# MacSet-L-V2_0_0_1.net
KiCad netlist of a schematic drawn in Altium Designer
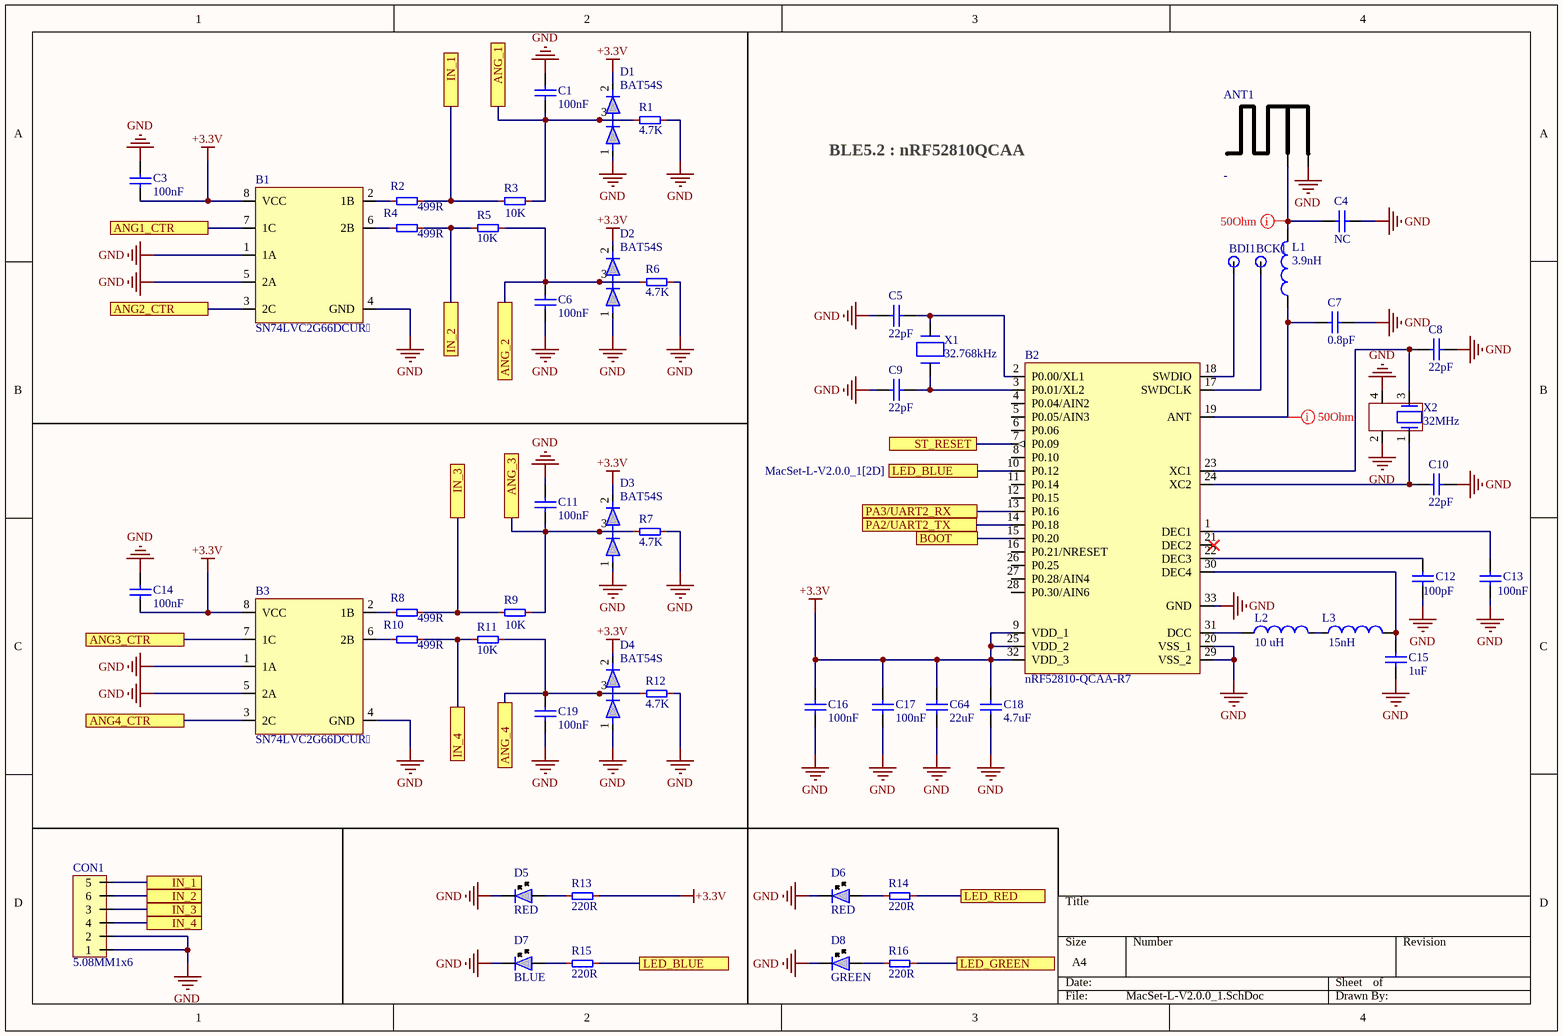
[diagram p0: MacSet-L-V2.0.0_1.SchDoc]

(export (version "E")
  (design (tool "Eeschema 10.0.6"))
  (components
    (comp (ref "ANT1")
      (value "-")
      (footprint "2.4GHz PCB Anttenna")
      (description "2.4GHq Inverted F antenna 1.6mm Thikness")
      (libsource (lib "macnman_2.0") (part "2.4GHz Antenna"))
    )
    (comp (ref "B1")
      (value "SN74LVC2G66DCUR")
      (footprint "SOP50P310X90-8N")
      (description "2-Channel, 1:1 Analog Switch with Low On-State Resistance")
      (fields
        (field (name "MANUFACTURER") "Texas Instruments")
        (field (name "MANUFACTURER_PART_NUMBER") "SN74LVC2G66DCUR")
      )
      (libsource (lib "macnman_2.0") (part "SN74LVC2G66DCUR"))
    )
    (comp (ref "B2")
      (value "nRF52810-QCAA-R7")
      (footprint "QFN50P500X500X95-33N")
      (fields (field (name "MANUFACTURER") "Nordic Semiconductor"))
      (libsource (lib "macnman_2.0") (part "nRF52810-QCAA-R7"))
    )
    (comp (ref "B3")
      (value "SN74LVC2G66DCUR")
      (footprint "SOP50P310X90-8N")
      (description "2-Channel, 1:1 Analog Switch with Low On-State Resistance")
      (fields
        (field (name "MANUFACTURER") "Texas Instruments")
        (field (name "MANUFACTURER_PART_NUMBER") "SN74LVC2G66DCUR")
      )
      (libsource (lib "macnman_2.0") (part "SN74LVC2G66DCUR"))
    )
    (comp (ref "BCK1")
      (value "-")
      (footprint "TH_Pad")
      (description "Through Hole pad 1mm 0.5mm Hole")
      (libsource (lib "macnman_2.0") (part "TH_PAD"))
    )
    (comp (ref "BDI1")
      (value "-")
      (footprint "TH_Pad")
      (description "Through Hole pad 1mm 0.5mm Hole")
      (libsource (lib "macnman_2.0") (part "TH_PAD"))
    )
    (comp (ref "C1")
      (value "100nF")
      (footprint "CAP0402")
      (description "Ceramic Capacitor C0G, NP0 0402 100nF 35V")
      (fields
        (field (name "MANUFACTURER_PART_NUMBER") "GRM155R61A104KA01J")
        (field (name "MANUFACTURER") "MURATA")
      )
      (libsource (lib "macnman_2.0") (part "Capa_0402"))
    )
    (comp (ref "C3")
      (value "100nF")
      (footprint "CAP0402")
      (description "Ceramic Capacitor C0G, NP0 0402 100nF 35V")
      (fields
        (field (name "MANUFACTURER_PART_NUMBER") "GRM155R61A104KA01J")
        (field (name "MANUFACTURER") "MURATA")
      )
      (libsource (lib "macnman_2.0") (part "Capa_0402"))
    )
    (comp (ref "C4") (value "NC") (footprint "CAP0402") (libsource (lib "macnman_2.0") (part "Capa_0402")))
    (comp (ref "C5")
      (value "22pF")
      (footprint "CAP0402")
      (description "Multilayer Ceramic Capacitors MLCC - SMD/SMT 50 V 22pF C0G 0402 5%")
      (fields
        (field (name "MANUFACTURER_PART_NUMBER") "GCM1555C1H220JA16D")
        (field (name "MANUFACTURER") "Murata")
      )
      (libsource (lib "macnman_2.0") (part "Capa_0402"))
    )
    (comp (ref "C6")
      (value "100nF")
      (footprint "CAP0402")
      (description "Ceramic Capacitor C0G, NP0 0402 100nF 35V")
      (fields
        (field (name "MANUFACTURER_PART_NUMBER") "GRM155R61A104KA01J")
        (field (name "MANUFACTURER") "MURATA")
      )
      (libsource (lib "macnman_2.0") (part "Capa_0402"))
    )
    (comp (ref "C7")
      (value "0.8pF")
      (footprint "CAP0402")
      (description "Ceramic Capacitor C0G, NP0 0402 0.8pF 50V")
      (fields
        (field (name "MANUFACTURER_PART_NUMBER") "CC0402BRNPO9BNR80")
        (field (name "MANUFACTURER") "YAGEO")
      )
      (libsource (lib "macnman_2.0") (part "Capa_0402"))
    )
    (comp (ref "C8")
      (value "22pF")
      (footprint "CAP0402")
      (description "Multilayer Ceramic Capacitors MLCC - SMD/SMT 50 V 22pF C0G 0402 5%")
      (fields
        (field (name "MANUFACTURER_PART_NUMBER") "GCM1555C1H220JA16D")
        (field (name "MANUFACTURER") "Murata")
      )
      (libsource (lib "macnman_2.0") (part "Capa_0402"))
    )
    (comp (ref "C9")
      (value "22pF")
      (footprint "CAP0402")
      (description "Multilayer Ceramic Capacitors MLCC - SMD/SMT 50 V 22pF C0G 0402 5%")
      (fields
        (field (name "MANUFACTURER_PART_NUMBER") "GCM1555C1H220JA16D")
        (field (name "MANUFACTURER") "Murata")
      )
      (libsource (lib "macnman_2.0") (part "Capa_0402"))
    )
    (comp (ref "C10")
      (value "22pF")
      (footprint "CAP0402")
      (description "Multilayer Ceramic Capacitors MLCC - SMD/SMT 50 V 22pF C0G 0402 5%")
      (fields
        (field (name "MANUFACTURER_PART_NUMBER") "GCM1555C1H220JA16D")
        (field (name "MANUFACTURER") "Murata")
      )
      (libsource (lib "macnman_2.0") (part "Capa_0402"))
    )
    (comp (ref "C11")
      (value "100nF")
      (footprint "CAP0402")
      (description "Ceramic Capacitor C0G, NP0 0402 100nF 35V")
      (fields
        (field (name "MANUFACTURER_PART_NUMBER") "GRM155R61A104KA01J")
        (field (name "MANUFACTURER") "MURATA")
      )
      (libsource (lib "macnman_2.0") (part "Capa_0402"))
    )
    (comp (ref "C12")
      (value "100pF")
      (footprint "CAP0402")
      (description "Ceramic Capacitor C0G, NP0 0402 100pF 50V")
      (fields
        (field (name "MANUFACTURER_PART_NUMBER") "GRM1555C1H101GA01D")
        (field (name "MANUFACTURER") "MURATA")
      )
      (libsource (lib "macnman_2.0") (part "Capa_0402"))
    )
    (comp (ref "C13")
      (value "100nF")
      (footprint "CAP0402")
      (description "Ceramic Capacitor X7R 0402 100nF 16V")
      (fields
        (field (name "MANUFACTURER_PART_NUMBER") "GRM155R71C104JA88D")
        (field (name "MANUFACTURER") "MURATA")
      )
      (libsource (lib "macnman_2.0") (part "Capa_0402"))
    )
    (comp (ref "C14")
      (value "100nF")
      (footprint "CAP0402")
      (description "Ceramic Capacitor C0G, NP0 0402 100nF 35V")
      (fields
        (field (name "MANUFACTURER_PART_NUMBER") "GRM155R61A104KA01J")
        (field (name "MANUFACTURER") "MURATA")
      )
      (libsource (lib "macnman_2.0") (part "Capa_0402"))
    )
    (comp (ref "C15")
      (value "1uF")
      (footprint "CAP0603")
      (description "MLCC - SMD/SMT 1 uF 16 VDC 10% 0603 X5R")
      (fields
        (field (name "MANUFACTURER_PART_NUMBER") "GRM188R61C105MA12D")
        (field (name "MANUFACTURER") "MURATA")
      )
      (libsource (lib "macnman_2.0") (part "Capa_0603"))
    )
    (comp (ref "C16")
      (value "100nF")
      (footprint "CAP0402")
      (description "Ceramic Capacitor X7R 0402 100nF 16V")
      (fields
        (field (name "MANUFACTURER_PART_NUMBER") "GRM155R71C104JA88D")
        (field (name "MANUFACTURER") "MURATA")
      )
      (libsource (lib "macnman_2.0") (part "Capa_0402"))
    )
    (comp (ref "C17")
      (value "100nF")
      (footprint "CAP0402")
      (description "Ceramic Capacitor X7R 0402 100nF 16V")
      (fields
        (field (name "MANUFACTURER_PART_NUMBER") "GRM155R71C104JA88D")
        (field (name "MANUFACTURER") "MURATA")
      )
      (libsource (lib "macnman_2.0") (part "Capa_0402"))
    )
    (comp (ref "C18")
      (value "4.7uF")
      (footprint "CAP0603")
      (description "MLCC - SMD/SMT 4.7 uF 16 VDC 10% 0603 X5R")
      (fields
        (field (name "MANUFACTURER_PART_NUMBER") "CL10A475KQ8NNNC")
        (field (name "MANUFACTURER") "Samsung Electro-Mechanics")
      )
      (libsource (lib "macnman_2.0") (part "Capa_0603"))
    )
    (comp (ref "C19")
      (value "100nF")
      (footprint "CAP0402")
      (description "Ceramic Capacitor C0G, NP0 0402 100nF 35V")
      (fields
        (field (name "MANUFACTURER_PART_NUMBER") "GRM155R61A104KA01J")
        (field (name "MANUFACTURER") "MURATA")
      )
      (libsource (lib "macnman_2.0") (part "Capa_0402"))
    )
    (comp (ref "C64")
      (value "22uF")
      (footprint "CAP0805")
      (description "MLCC - SMD/SMT 22uF 10VDC 20% 0805 X6S")
      (fields
        (field (name "MANUFACTURER_PART_NUMBER") "CC0805KKX7R6BB226")
        (field (name "MANUFACTURER") "MURATA")
      )
      (libsource (lib "macnman_2.0") (part "Capa_0805"))
    )
    (comp (ref "CON1")
      (value "5.08MM1x6")
      (footprint "Screw Terminal Block 5.08x6")
      (description "5.08mm 1*6 Screw Terminal Block")
      (fields (field (name "MANUFACTURER") "XINYA"))
      (libsource (lib "macnman_2.0") (part "Screw Terminal Block 6x1 5.08mm"))
    )
    (comp (ref "D1")
      (value "BAT54S")
      (footprint "SOT23")
      (description "BAT54S Schottky Diodes & Rectifiers SS SHKY DIO 30V TR")
      (fields (field (name "MANUFACTURER_PART_NUMBER") "Nexperia") (field (name "MANUFACTURER") "BAT54S,235"))
      (libsource (lib "macnman_2.0") (part "BAT54SWT1G"))
    )
    (comp (ref "D2")
      (value "BAT54S")
      (footprint "SOT23")
      (description "BAT54S Schottky Diodes & Rectifiers SS SHKY DIO 30V TR")
      (fields (field (name "MANUFACTURER_PART_NUMBER") "Nexperia") (field (name "MANUFACTURER") "BAT54S,235"))
      (libsource (lib "macnman_2.0") (part "BAT54SWT1G"))
    )
    (comp (ref "D3")
      (value "BAT54S")
      (footprint "SOT23")
      (description "BAT54S Schottky Diodes & Rectifiers SS SHKY DIO 30V TR")
      (fields (field (name "MANUFACTURER_PART_NUMBER") "Nexperia") (field (name "MANUFACTURER") "BAT54S,235"))
      (libsource (lib "macnman_2.0") (part "BAT54SWT1G"))
    )
    (comp (ref "D4")
      (value "BAT54S")
      (footprint "SOT23")
      (description "BAT54S Schottky Diodes & Rectifiers SS SHKY DIO 30V TR")
      (fields (field (name "MANUFACTURER_PART_NUMBER") "Nexperia") (field (name "MANUFACTURER") "BAT54S,235"))
      (libsource (lib "macnman_2.0") (part "BAT54SWT1G"))
    )
    (comp (ref "D5")
      (value "RED")
      (footprint "LED_3MM")
      (description "LED 3MM Through Hole RED")
      (libsource (lib "macnman_2.0") (part "LED_3MM"))
    )
    (comp (ref "D6")
      (value "RED")
      (footprint "LED_3MM")
      (description "LED 3MM Through Hole RED")
      (libsource (lib "macnman_2.0") (part "LED_3MM"))
    )
    (comp (ref "D7")
      (value "BLUE")
      (footprint "LED_3MM")
      (description "LED 3MM Through Hole BLUE")
      (libsource (lib "macnman_2.0") (part "LED_3MM"))
    )
    (comp (ref "D8")
      (value "GREEN")
      (footprint "LED_3MM")
      (description "LED 3MM Through Hole GREEN")
      (libsource (lib "macnman_2.0") (part "LED_3MM"))
    )
    (comp (ref "L1")
      (value "3.9nH")
      (footprint "IND_0402")
      (description "3.9nH High frequency chip inductor ±5%  0402")
      (fields
        (field (name "MANUFACTURER_PART_NUMBER") "LQG15HS3N9B02D")
        (field (name "MANUFACTURER") "Murata")
      )
      (libsource (lib "macnman_2.0") (part "Inductor"))
    )
    (comp (ref "L2")
      (value "10 uH")
      (footprint "IND_0603")
      (description "250mA 10uH ±20% 90mΩ 0603 Inductors")
      (fields
        (field (name "MANUFACTURER_PART_NUMBER") "MLZ1608M100WT000")
        (field (name "MANUFACTURER") "TDK")
      )
      (libsource (lib "macnman_2.0") (part "MCD-01330"))
    )
    (comp (ref "L3")
      (value "15nH")
      (footprint "IND_0402")
      (description "400mA 15nH ±5% 350mΩ 0402 Inductors")
      (fields
        (field (name "MANUFACTURER_PART_NUMBER") "MLG1005S15NJT000")
        (field (name "MANUFACTURER") "Murata")
      )
      (libsource (lib "macnman_2.0") (part "MCD-01330"))
    )
    (comp (ref "R1")
      (value "4.7K")
      (footprint "RESC0402")
      (description "Thin Film Resistors - SMD 4.7Kohms 0.1% 0402 25ppm")
      (fields
        (field (name "MANUFACTURER_PART_NUMBER") "RT0402BRD074K7L")
        (field (name "MANUFACTURER") "YAGEO")
      )
      (libsource (lib "macnman_2.0") (part "RES_0402"))
    )
    (comp (ref "R2")
      (value "499R")
      (footprint "RESC0805")
      (description "Thin Film Resistors - SMD 499ohms 0.1% 25ppm")
      (fields
        (field (name "MANUFACTURER_PART_NUMBER") "TNPW0805499RBEEA")
        (field (name "MANUFACTURER") "Vishay")
      )
      (libsource (lib "macnman_2.0") (part "RES_0805"))
    )
    (comp (ref "R3")
      (value "10K")
      (footprint "RESC0402")
      (description "Thick Film Resistors - SMD 1/16watt 10Kohms 0.1% 0402 Commercial Use")
      (fields
        (field (name "MANUFACTURER_PART_NUMBER") "MCS04020D1002BE000")
        (field (name "MANUFACTURER") "Vishay")
      )
      (libsource (lib "macnman_2.0") (part "RES_0402"))
    )
    (comp (ref "R4")
      (value "499R")
      (footprint "RESC0805")
      (description "Thin Film Resistors - SMD 499ohms 0.1% 25ppm")
      (fields
        (field (name "MANUFACTURER_PART_NUMBER") "TNPW0805499RBEEA")
        (field (name "MANUFACTURER") "Vishay")
      )
      (libsource (lib "macnman_2.0") (part "RES_0805"))
    )
    (comp (ref "R5")
      (value "10K")
      (footprint "RESC0402")
      (description "Thick Film Resistors - SMD 1/16watt 10Kohms 0.1% 0402 Commercial Use")
      (fields
        (field (name "MANUFACTURER_PART_NUMBER") "MCS04020D1002BE000")
        (field (name "MANUFACTURER") "Vishay")
      )
      (libsource (lib "macnman_2.0") (part "RES_0402"))
    )
    (comp (ref "R6")
      (value "4.7K")
      (footprint "RESC0402")
      (description "Thin Film Resistors - SMD 4.7Kohms 0.1% 0402 25ppm")
      (fields
        (field (name "MANUFACTURER_PART_NUMBER") "RT0402BRD074K7L")
        (field (name "MANUFACTURER") "YAGEO")
      )
      (libsource (lib "macnman_2.0") (part "RES_0402"))
    )
    (comp (ref "R7")
      (value "4.7K")
      (footprint "RESC0402")
      (description "Thin Film Resistors - SMD 4.7Kohms 0.1% 0402 25ppm")
      (fields
        (field (name "MANUFACTURER_PART_NUMBER") "RT0402BRD074K7L")
        (field (name "MANUFACTURER") "YAGEO")
      )
      (libsource (lib "macnman_2.0") (part "RES_0402"))
    )
    (comp (ref "R8")
      (value "499R")
      (footprint "RESC0805")
      (description "Thin Film Resistors - SMD 499ohms 0.1% 25ppm")
      (fields
        (field (name "MANUFACTURER_PART_NUMBER") "TNPW0805499RBEEA")
        (field (name "MANUFACTURER") "Vishay")
      )
      (libsource (lib "macnman_2.0") (part "RES_0805"))
    )
    (comp (ref "R9")
      (value "10K")
      (footprint "RESC0402")
      (description "Thick Film Resistors - SMD 1/16watt 10Kohms 0.1% 0402 Commercial Use")
      (fields
        (field (name "MANUFACTURER_PART_NUMBER") "MCS04020D1002BE000")
        (field (name "MANUFACTURER") "Vishay")
      )
      (libsource (lib "macnman_2.0") (part "RES_0402"))
    )
    (comp (ref "R10")
      (value "499R")
      (footprint "RESC0805")
      (description "Thin Film Resistors - SMD 499ohms 0.1% 25ppm")
      (fields
        (field (name "MANUFACTURER_PART_NUMBER") "TNPW0805499RBEEA")
        (field (name "MANUFACTURER") "Vishay")
      )
      (libsource (lib "macnman_2.0") (part "RES_0805"))
    )
    (comp (ref "R11")
      (value "10K")
      (footprint "RESC0402")
      (description "Thick Film Resistors - SMD 1/16watt 10Kohms 0.1% 0402 Commercial Use")
      (fields
        (field (name "MANUFACTURER_PART_NUMBER") "MCS04020D1002BE000")
        (field (name "MANUFACTURER") "Vishay")
      )
      (libsource (lib "macnman_2.0") (part "RES_0402"))
    )
    (comp (ref "R12")
      (value "4.7K")
      (footprint "RESC0402")
      (description "Thin Film Resistors - SMD 4.7Kohms 0.1% 0402 25ppm")
      (fields
        (field (name "MANUFACTURER_PART_NUMBER") "RT0402BRD074K7L")
        (field (name "MANUFACTURER") "YAGEO")
      )
      (libsource (lib "macnman_2.0") (part "RES_0402"))
    )
    (comp (ref "R13")
      (value "220R")
      (footprint "RESC0402")
      (description "Thick Film Resistors - SMD 1/16watt 220R 0402 1% Commercial Use")
      (fields
        (field (name "MANUFACTURER_PART_NUMBER") "RC0402FR-07220RL")
        (field (name "MANUFACTURER") "Vishay")
      )
      (libsource (lib "macnman_2.0") (part "RES_0402"))
    )
    (comp (ref "R14")
      (value "220R")
      (footprint "RESC0402")
      (description "Thick Film Resistors - SMD 1/16watt 220R 0402 1% Commercial Use")
      (fields
        (field (name "MANUFACTURER_PART_NUMBER") "RC0402FR-07220RL")
        (field (name "MANUFACTURER") "Vishay")
      )
      (libsource (lib "macnman_2.0") (part "RES_0402"))
    )
    (comp (ref "R15")
      (value "220R")
      (footprint "RESC0402")
      (description "Thick Film Resistors - SMD 1/16watt 220R 0402 1% Commercial Use")
      (fields
        (field (name "MANUFACTURER_PART_NUMBER") "RC0402FR-07220RL")
        (field (name "MANUFACTURER") "Vishay")
      )
      (libsource (lib "macnman_2.0") (part "RES_0402"))
    )
    (comp (ref "R16")
      (value "220R")
      (footprint "RESC0402")
      (description "Thick Film Resistors - SMD 1/16watt 220R 0402 1% Commercial Use")
      (fields
        (field (name "MANUFACTURER_PART_NUMBER") "RC0402FR-07220RL")
        (field (name "MANUFACTURER") "Vishay")
      )
      (libsource (lib "macnman_2.0") (part "RES_0402"))
    )
    (comp (ref "X1")
      (value "32.768kHz")
      (footprint "OSC_3215")
      (description "Crystal Osc 3215 32.768kHz 12pF")
      (fields
        (field (name "MANUFACTURER_PART_NUMBER") "ECS-.327-12.5-34B-TR")
        (field (name "MANUFACTURER") "ECS")
      )
      (libsource (lib "macnman_2.0") (part "OSC_2012"))
    )
    (comp (ref "X2")
      (value "32MHz")
      (footprint "OSC_2016")
      (description "Crystal Osc 2016 32MHz 12pF  60R")
      (fields
        (field (name "MANUFACTURER_PART_NUMBER") "XRCGB32M000F1SADR0")
        (field (name "MANUFACTURER") "Murata")
      )
      (libsource (lib "macnman_2.0") (part "OSC_2016"))
    )
  )
  (nets
    (net (code "1") (name "+3.3V") (class "Default")
      (node (ref "B1") (pin "8") (pinfunction "VCC_8") (pintype "passive"))
      (node (ref "B2") (pin "25") (pinfunction "VDD_2_25") (pintype "passive"))
      (node (ref "B2") (pin "32") (pinfunction "VDD_3_32") (pintype "passive"))
      (node (ref "B2") (pin "9") (pinfunction "VDD_1_9") (pintype "passive"))
      (node (ref "B3") (pin "8") (pinfunction "VCC_8") (pintype "passive"))
      (node (ref "C14") (pin "2") (pinfunction "2_2") (pintype "passive"))
      (node (ref "C16") (pin "2") (pinfunction "2_2") (pintype "passive"))
      (node (ref "C17") (pin "2") (pinfunction "2_2") (pintype "passive"))
      (node (ref "C18") (pin "2") (pinfunction "2_2") (pintype "passive"))
      (node (ref "C3") (pin "2") (pinfunction "2_2") (pintype "passive"))
      (node (ref "C64") (pin "2") (pinfunction "2_2") (pintype "passive"))
      (node (ref "D1") (pin "2") (pinfunction "2_2") (pintype "passive"))
      (node (ref "D2") (pin "2") (pinfunction "2_2") (pintype "passive"))
      (node (ref "D3") (pin "2") (pinfunction "2_2") (pintype "passive"))
      (node (ref "D4") (pin "2") (pinfunction "2_2") (pintype "passive"))
      (node (ref "R13") (pin "1") (pinfunction "1_1") (pintype "passive"))
    )
    (net (code "2") (name "/ANG1_CTR") (class "Default")
      (node (ref "B1") (pin "7") (pinfunction "1C_7") (pintype "passive"))
    )
    (net (code "3") (name "/ANG2_CTR") (class "Default")
      (node (ref "B1") (pin "3") (pinfunction "2C_3") (pintype "passive"))
    )
    (net (code "4") (name "/ANG3_CTR") (class "Default")
      (node (ref "B3") (pin "7") (pinfunction "1C_7") (pintype "passive"))
    )
    (net (code "5") (name "/ANG4_CTR") (class "Default")
      (node (ref "B3") (pin "3") (pinfunction "2C_3") (pintype "passive"))
    )
    (net (code "6") (name "/ANG_1") (class "Default")
      (node (ref "C1") (pin "1") (pinfunction "1_1") (pintype "passive"))
      (node (ref "D1") (pin "3") (pinfunction "3_3") (pintype "passive"))
      (node (ref "R1") (pin "2") (pinfunction "2_2") (pintype "passive"))
      (node (ref "R3") (pin "1") (pinfunction "1_1") (pintype "passive"))
    )
    (net (code "7") (name "/ANG_2") (class "Default")
      (node (ref "C6") (pin "2") (pinfunction "2_2") (pintype "passive"))
      (node (ref "D2") (pin "3") (pinfunction "3_3") (pintype "passive"))
      (node (ref "R5") (pin "1") (pinfunction "1_1") (pintype "passive"))
      (node (ref "R6") (pin "2") (pinfunction "2_2") (pintype "passive"))
    )
    (net (code "8") (name "/ANG_3") (class "Default")
      (node (ref "C11") (pin "1") (pinfunction "1_1") (pintype "passive"))
      (node (ref "D3") (pin "3") (pinfunction "3_3") (pintype "passive"))
      (node (ref "R7") (pin "2") (pinfunction "2_2") (pintype "passive"))
      (node (ref "R9") (pin "1") (pinfunction "1_1") (pintype "passive"))
    )
    (net (code "9") (name "/ANG_4") (class "Default")
      (node (ref "C19") (pin "2") (pinfunction "2_2") (pintype "passive"))
      (node (ref "D4") (pin "3") (pinfunction "3_3") (pintype "passive"))
      (node (ref "R11") (pin "1") (pinfunction "1_1") (pintype "passive"))
      (node (ref "R12") (pin "2") (pinfunction "2_2") (pintype "passive"))
    )
    (net (code "10") (name "/BOOT") (class "Default")
      (node (ref "B2") (pin "15") (pinfunction "P0.20_15") (pintype "passive"))
    )
    (net (code "11") (name "/IN_1") (class "Default")
      (node (ref "CON1") (pin "5") (pinfunction "5_5") (pintype "passive"))
      (node (ref "R2") (pin "2") (pinfunction "2_2") (pintype "passive"))
      (node (ref "R3") (pin "2") (pinfunction "2_2") (pintype "passive"))
    )
    (net (code "12") (name "/IN_2") (class "Default")
      (node (ref "CON1") (pin "6") (pinfunction "6_6") (pintype "passive"))
      (node (ref "R4") (pin "2") (pinfunction "2_2") (pintype "passive"))
      (node (ref "R5") (pin "2") (pinfunction "2_2") (pintype "passive"))
    )
    (net (code "13") (name "/IN_3") (class "Default")
      (node (ref "CON1") (pin "3") (pinfunction "3_3") (pintype "passive"))
      (node (ref "R8") (pin "2") (pinfunction "2_2") (pintype "passive"))
      (node (ref "R9") (pin "2") (pinfunction "2_2") (pintype "passive"))
    )
    (net (code "14") (name "/IN_4") (class "Default")
      (node (ref "CON1") (pin "4") (pinfunction "4_4") (pintype "passive"))
      (node (ref "R10") (pin "2") (pinfunction "2_2") (pintype "passive"))
      (node (ref "R11") (pin "2") (pinfunction "2_2") (pintype "passive"))
    )
    (net (code "15") (name "/LED_BLUE") (class "Default")
      (node (ref "B2") (pin "10") (pinfunction "P0.12_10") (pintype "passive"))
      (node (ref "R15") (pin "1") (pinfunction "1_1") (pintype "passive"))
    )
    (net (code "16") (name "/LED_GREEN") (class "Default")
      (node (ref "R16") (pin "1") (pinfunction "1_1") (pintype "passive"))
    )
    (net (code "17") (name "/LED_RED") (class "Default")
      (node (ref "R14") (pin "1") (pinfunction "1_1") (pintype "passive"))
    )
    (net (code "18") (name "/PA2{slash}UART2_TX") (class "Default")
      (node (ref "B2") (pin "14") (pinfunction "P0.18_14") (pintype "passive"))
    )
    (net (code "19") (name "/PA3{slash}UART2_RX") (class "Default")
      (node (ref "B2") (pin "13") (pinfunction "P0.16_13") (pintype "passive"))
    )
    (net (code "20") (name "/ST_RESET") (class "Default")
      (node (ref "B2") (pin "7") (pinfunction "P0.09_7") (pintype "output"))
    )
    (net (code "21") (name "GND") (class "Default")
      (node (ref "ANT1") (pin "2") (pinfunction "GND_2") (pintype "passive"))
      (node (ref "B1") (pin "1") (pinfunction "1A_1") (pintype "passive"))
      (node (ref "B1") (pin "4") (pinfunction "GND_4") (pintype "passive"))
      (node (ref "B1") (pin "5") (pinfunction "2A_5") (pintype "passive"))
      (node (ref "B2") (pin "20") (pinfunction "VSS_1_20") (pintype "passive"))
      (node (ref "B2") (pin "29") (pinfunction "VSS_2_29") (pintype "passive"))
      (node (ref "B2") (pin "33") (pinfunction "GND_33") (pintype "passive"))
      (node (ref "B3") (pin "1") (pinfunction "1A_1") (pintype "passive"))
      (node (ref "B3") (pin "4") (pinfunction "GND_4") (pintype "passive"))
      (node (ref "B3") (pin "5") (pinfunction "2A_5") (pintype "passive"))
      (node (ref "C1") (pin "2") (pinfunction "2_2") (pintype "passive"))
      (node (ref "C10") (pin "2") (pinfunction "2_2") (pintype "passive"))
      (node (ref "C11") (pin "2") (pinfunction "2_2") (pintype "passive"))
      (node (ref "C12") (pin "2") (pinfunction "2_2") (pintype "passive"))
      (node (ref "C13") (pin "2") (pinfunction "2_2") (pintype "passive"))
      (node (ref "C14") (pin "1") (pinfunction "1_1") (pintype "passive"))
      (node (ref "C15") (pin "1") (pinfunction "1_1") (pintype "passive"))
      (node (ref "C16") (pin "1") (pinfunction "1_1") (pintype "passive"))
      (node (ref "C17") (pin "1") (pinfunction "1_1") (pintype "passive"))
      (node (ref "C18") (pin "1") (pinfunction "1_1") (pintype "passive"))
      (node (ref "C19") (pin "1") (pinfunction "1_1") (pintype "passive"))
      (node (ref "C3") (pin "1") (pinfunction "1_1") (pintype "passive"))
      (node (ref "C4") (pin "1") (pinfunction "1_1") (pintype "passive"))
      (node (ref "C5") (pin "1") (pinfunction "1_1") (pintype "passive"))
      (node (ref "C6") (pin "1") (pinfunction "1_1") (pintype "passive"))
      (node (ref "C64") (pin "1") (pinfunction "1_1") (pintype "passive"))
      (node (ref "C7") (pin "1") (pinfunction "1_1") (pintype "passive"))
      (node (ref "C8") (pin "2") (pinfunction "2_2") (pintype "passive"))
      (node (ref "C9") (pin "1") (pinfunction "1_1") (pintype "passive"))
      (node (ref "CON1") (pin "1") (pinfunction "1_1") (pintype "passive"))
      (node (ref "CON1") (pin "2") (pinfunction "2_2") (pintype "passive"))
      (node (ref "D1") (pin "1") (pinfunction "1_1") (pintype "passive"))
      (node (ref "D2") (pin "1") (pinfunction "1_1") (pintype "passive"))
      (node (ref "D3") (pin "1") (pinfunction "1_1") (pintype "passive"))
      (node (ref "D4") (pin "1") (pinfunction "1_1") (pintype "passive"))
      (node (ref "D5") (pin "1") (pinfunction "K_1") (pintype "passive"))
      (node (ref "D6") (pin "1") (pinfunction "K_1") (pintype "passive"))
      (node (ref "D7") (pin "1") (pinfunction "K_1") (pintype "passive"))
      (node (ref "D8") (pin "1") (pinfunction "K_1") (pintype "passive"))
      (node (ref "R1") (pin "1") (pinfunction "1_1") (pintype "passive"))
      (node (ref "R12") (pin "1") (pinfunction "1_1") (pintype "passive"))
      (node (ref "R6") (pin "1") (pinfunction "1_1") (pintype "passive"))
      (node (ref "R7") (pin "1") (pinfunction "1_1") (pintype "passive"))
      (node (ref "X2") (pin "2") (pinfunction "2_2") (pintype "passive"))
      (node (ref "X2") (pin "4") (pinfunction "4_4") (pintype "passive"))
    )
    (net (code "22") (name "Net-(ANT1-FEED)") (class "Default")
      (node (ref "ANT1") (pin "1") (pinfunction "FEED_1") (pintype "passive"))
      (node (ref "C4") (pin "2") (pinfunction "2_2") (pintype "passive"))
      (node (ref "L1") (pin "2") (pintype "passive"))
    )
    (net (code "23") (name "Net-(B1-1B)") (class "Default")
      (node (ref "B1") (pin "2") (pinfunction "1B_2") (pintype "passive"))
      (node (ref "R2") (pin "1") (pinfunction "1_1") (pintype "passive"))
    )
    (net (code "24") (name "Net-(B1-2B)") (class "Default")
      (node (ref "B1") (pin "6") (pinfunction "2B_6") (pintype "passive"))
      (node (ref "R4") (pin "1") (pinfunction "1_1") (pintype "passive"))
    )
    (net (code "25") (name "Net-(B2-ANT)") (class "Default")
      (node (ref "B2") (pin "19") (pinfunction "ANT_19") (pintype "passive"))
      (node (ref "C7") (pin "2") (pinfunction "2_2") (pintype "passive"))
      (node (ref "L1") (pin "1") (pintype "passive"))
    )
    (net (code "26") (name "Net-(B2-DCC)") (class "Default")
      (node (ref "B2") (pin "31") (pinfunction "DCC_31") (pintype "passive"))
      (node (ref "L2") (pin "1") (pinfunction "1_1") (pintype "passive"))
    )
    (net (code "27") (name "Net-(B2-DEC1)") (class "Default")
      (node (ref "B2") (pin "1") (pinfunction "DEC1_1") (pintype "passive"))
      (node (ref "C13") (pin "1") (pinfunction "1_1") (pintype "passive"))
    )
    (net (code "28") (name "Net-(B2-DEC3)") (class "Default")
      (node (ref "B2") (pin "22") (pinfunction "DEC3_22") (pintype "passive"))
      (node (ref "C12") (pin "1") (pinfunction "1_1") (pintype "passive"))
    )
    (net (code "29") (name "Net-(B2-DEC4)") (class "Default")
      (node (ref "B2") (pin "30") (pinfunction "DEC4_30") (pintype "passive"))
      (node (ref "C15") (pin "2") (pinfunction "2_2") (pintype "passive"))
      (node (ref "L3") (pin "2") (pinfunction "2_2") (pintype "passive"))
    )
    (net (code "30") (name "Net-(B2-P0.00{slash}XL1)") (class "Default")
      (node (ref "B2") (pin "2") (pinfunction "P0.00/XL1_2") (pintype "passive"))
      (node (ref "C5") (pin "2") (pinfunction "2_2") (pintype "passive"))
      (node (ref "X1") (pin "2") (pinfunction "X2_2") (pintype "passive"))
    )
    (net (code "31") (name "Net-(B2-P0.01{slash}XL2)") (class "Default")
      (node (ref "B2") (pin "3") (pinfunction "P0.01/XL2_3") (pintype "passive"))
      (node (ref "C9") (pin "2") (pinfunction "2_2") (pintype "passive"))
      (node (ref "X1") (pin "1") (pinfunction "X1_1") (pintype "passive"))
    )
    (net (code "32") (name "Net-(B2-SWDCLK)") (class "Default")
      (node (ref "B2") (pin "17") (pinfunction "SWDCLK_17") (pintype "passive"))
      (node (ref "BCK1") (pin "1") (pinfunction "1_1") (pintype "passive"))
    )
    (net (code "33") (name "Net-(B2-SWDIO)") (class "Default")
      (node (ref "B2") (pin "18") (pinfunction "SWDIO_18") (pintype "passive"))
      (node (ref "BDI1") (pin "1") (pinfunction "1_1") (pintype "passive"))
    )
    (net (code "34") (name "Net-(B2-XC1)") (class "Default")
      (node (ref "B2") (pin "23") (pinfunction "XC1_23") (pintype "passive"))
      (node (ref "C8") (pin "1") (pinfunction "1_1") (pintype "passive"))
      (node (ref "X2") (pin "3") (pinfunction "3_3") (pintype "passive"))
    )
    (net (code "35") (name "Net-(B2-XC2)") (class "Default")
      (node (ref "B2") (pin "24") (pinfunction "XC2_24") (pintype "passive"))
      (node (ref "C10") (pin "1") (pinfunction "1_1") (pintype "passive"))
      (node (ref "X2") (pin "1") (pinfunction "1_1") (pintype "passive"))
    )
    (net (code "36") (name "Net-(B3-1B)") (class "Default")
      (node (ref "B3") (pin "2") (pinfunction "1B_2") (pintype "passive"))
      (node (ref "R8") (pin "1") (pinfunction "1_1") (pintype "passive"))
    )
    (net (code "37") (name "Net-(B3-2B)") (class "Default")
      (node (ref "B3") (pin "6") (pinfunction "2B_6") (pintype "passive"))
      (node (ref "R10") (pin "1") (pinfunction "1_1") (pintype "passive"))
    )
    (net (code "38") (name "Net-(D5-A)") (class "Default")
      (node (ref "D5") (pin "2") (pinfunction "A_2") (pintype "passive"))
      (node (ref "R13") (pin "2") (pinfunction "2_2") (pintype "passive"))
    )
    (net (code "39") (name "Net-(D6-A)") (class "Default")
      (node (ref "D6") (pin "2") (pinfunction "A_2") (pintype "passive"))
      (node (ref "R14") (pin "2") (pinfunction "2_2") (pintype "passive"))
    )
    (net (code "40") (name "Net-(D7-A)") (class "Default")
      (node (ref "D7") (pin "2") (pinfunction "A_2") (pintype "passive"))
      (node (ref "R15") (pin "2") (pinfunction "2_2") (pintype "passive"))
    )
    (net (code "41") (name "Net-(D8-A)") (class "Default")
      (node (ref "D8") (pin "2") (pinfunction "A_2") (pintype "passive"))
      (node (ref "R16") (pin "2") (pinfunction "2_2") (pintype "passive"))
    )
    (net (code "42") (name "Net-(L2-Pad2)") (class "Default")
      (node (ref "L2") (pin "2") (pinfunction "2_2") (pintype "passive"))
      (node (ref "L3") (pin "1") (pinfunction "1_1") (pintype "passive"))
    )
    (net (code "43") (name "unconnected-(B2-DEC2-Pad21)") (class "Default")
      (node (ref "B2") (pin "21") (pinfunction "DEC2_21") (pintype "passive+no_connect"))
    )
    (net (code "44") (name "unconnected-(B2-P0.04{slash}AIN2-Pad4)") (class "Default")
      (node (ref "B2") (pin "4") (pinfunction "P0.04/AIN2_4") (pintype "passive"))
    )
    (net (code "45") (name "unconnected-(B2-P0.05{slash}AIN3-Pad5)") (class "Default")
      (node (ref "B2") (pin "5") (pinfunction "P0.05/AIN3_5") (pintype "passive"))
    )
    (net (code "46") (name "unconnected-(B2-P0.06-Pad6)") (class "Default")
      (node (ref "B2") (pin "6") (pinfunction "P0.06_6") (pintype "passive"))
    )
    (net (code "47") (name "unconnected-(B2-P0.10-Pad8)") (class "Default")
      (node (ref "B2") (pin "8") (pinfunction "P0.10_8") (pintype "passive"))
    )
    (net (code "48") (name "unconnected-(B2-P0.14-Pad11)") (class "Default")
      (node (ref "B2") (pin "11") (pinfunction "P0.14_11") (pintype "passive"))
    )
    (net (code "49") (name "unconnected-(B2-P0.15-Pad12)") (class "Default")
      (node (ref "B2") (pin "12") (pinfunction "P0.15_12") (pintype "passive"))
    )
    (net (code "50") (name "unconnected-(B2-P0.21{slash}NRESET-Pad16)") (class "Default")
      (node (ref "B2") (pin "16") (pinfunction "P0.21/NRESET_16") (pintype "passive"))
    )
    (net (code "51") (name "unconnected-(B2-P0.25-Pad26)") (class "Default")
      (node (ref "B2") (pin "26") (pinfunction "P0.25_26") (pintype "passive"))
    )
    (net (code "52") (name "unconnected-(B2-P0.28{slash}AIN4-Pad27)") (class "Default")
      (node (ref "B2") (pin "27") (pinfunction "P0.28/AIN4_27") (pintype "passive"))
    )
    (net (code "53") (name "unconnected-(B2-P0.30{slash}AIN6-Pad28)") (class "Default")
      (node (ref "B2") (pin "28") (pinfunction "P0.30/AIN6_28") (pintype "passive"))
    )
  )
)
